# fastedge.net
KiCad netlist of a schematic drawn in EAGLE
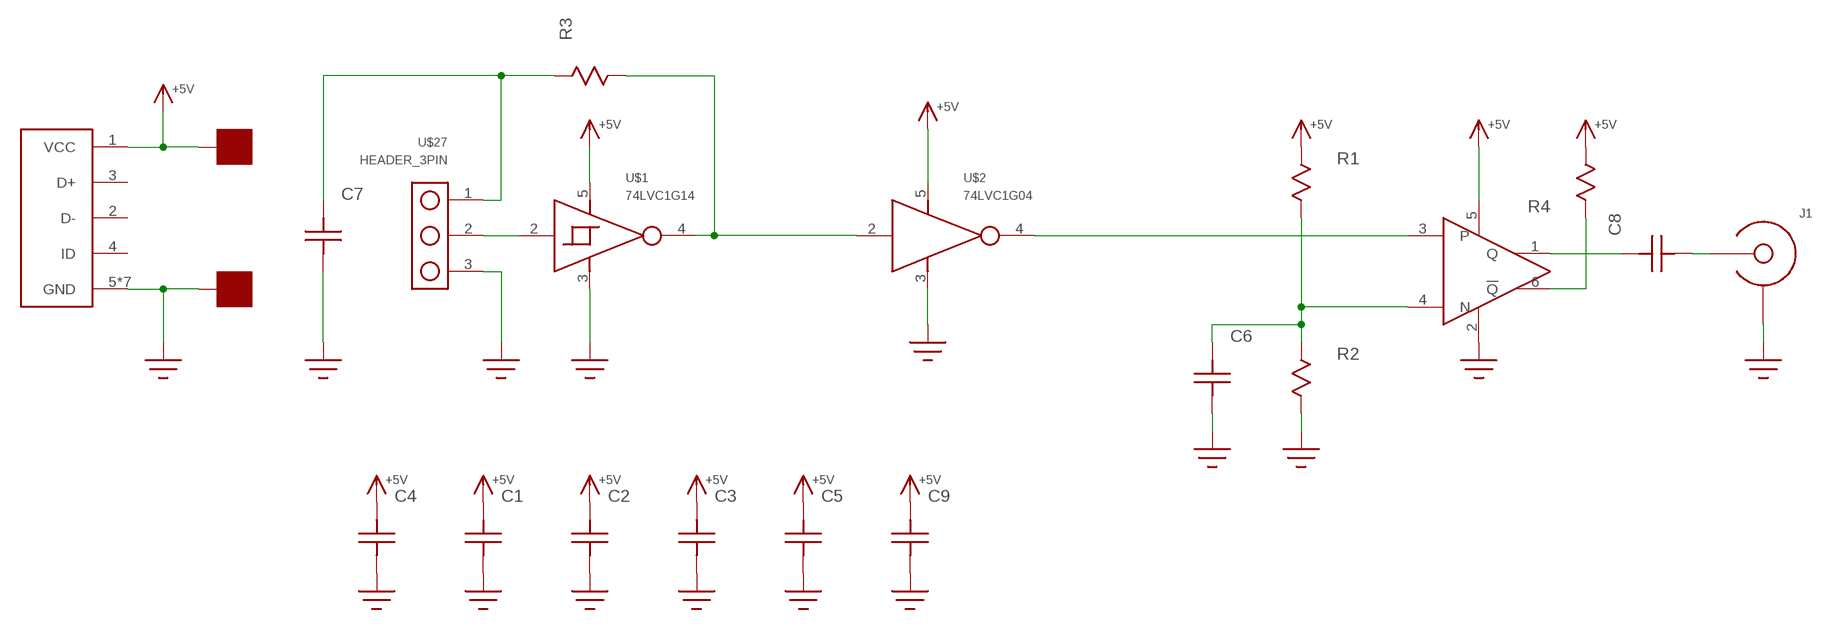
[diagram p0: schematic, sheet 1]

(export (version "E")
  (design (tool "Eeschema 10.0.6"))
  (components
    (comp (ref "C1")
      (value "C0603")
      (footprint "eagle-import:C0603")
      (libsource (lib "eagle-import") (part "C0603"))
    )
    (comp (ref "C2")
      (value "C0603")
      (footprint "eagle-import:C0603")
      (libsource (lib "eagle-import") (part "C0603"))
    )
    (comp (ref "C3")
      (value "C0603")
      (footprint "eagle-import:C0603")
      (libsource (lib "eagle-import") (part "C0603"))
    )
    (comp (ref "C4")
      (value "C0805")
      (footprint "eagle-import:0805")
      (libsource (lib "eagle-import") (part "C0805"))
    )
    (comp (ref "C5")
      (value "C0402_NO_THERMALS")
      (footprint "eagle-import:C0402_NO_THERMALS")
      (libsource (lib "eagle-import") (part "C0402_NO_THERMALS"))
    )
    (comp (ref "C6")
      (value "C0603")
      (footprint "eagle-import:C0603")
      (libsource (lib "eagle-import") (part "C0603"))
    )
    (comp (ref "C7")
      (value "C0603")
      (footprint "eagle-import:C0603")
      (libsource (lib "eagle-import") (part "C0603"))
    )
    (comp (ref "C8")
      (value "C0402_NO_THERMALS")
      (footprint "eagle-import:C0402_NO_THERMALS")
      (libsource (lib "eagle-import") (part "C0402_NO_THERMALS"))
    )
    (comp (ref "C9")
      (value "C0402_NO_THERMALS")
      (footprint "eagle-import:C0402_NO_THERMALS")
      (libsource (lib "eagle-import") (part "C0402_NO_THERMALS"))
    )
    (comp (ref "IC1")
      (value "ADCMP606")
      (footprint "eagle-import:SC70-6")
      (libsource (lib "eagle-import") (part "ADCMP606"))
    )
    (comp (ref "J1")
      (value "BNC_MALE_PCB")
      (footprint "eagle-import:BNC_MALE_PCB")
      (libsource (lib "eagle-import") (part "BNC_MALE_PCB"))
    )
    (comp (ref "R1")
      (value "R0603")
      (footprint "eagle-import:R0603")
      (libsource (lib "eagle-import") (part "R0603"))
    )
    (comp (ref "R2")
      (value "R0603")
      (footprint "eagle-import:R0603")
      (libsource (lib "eagle-import") (part "R0603"))
    )
    (comp (ref "R3")
      (value "R0603")
      (footprint "eagle-import:R0603")
      (libsource (lib "eagle-import") (part "R0603"))
    )
    (comp (ref "R4")
      (value "R0402")
      (footprint "eagle-import:0402")
      (libsource (lib "eagle-import") (part "R0402"))
    )
    (comp (ref "U$1")
      (value "74LVC1G14")
      (footprint "eagle-import:SOT23-5")
      (libsource (lib "eagle-import") (part "74LVC1G14"))
    )
    (comp (ref "U$2")
      (value "74LVC1G04")
      (footprint "eagle-import:SOT23-5")
      (libsource (lib "eagle-import") (part "74LVC1G04"))
    )
    (comp (ref "U$13")
      (value "USB_JACK")
      (footprint "eagle-import:FCI_MICRO_USB")
      (libsource (lib "eagle-import") (part "USB_JACK"))
    )
    (comp (ref "U$27")
      (value "HEADER_3PIN")
      (footprint "eagle-import:HEADER_3PIN")
      (libsource (lib "eagle-import") (part "HEADER_3PIN"))
    )
    (comp (ref "U$32")
      (value "PAD50MIL")
      (footprint "eagle-import:PAD_50MIL")
      (libsource (lib "eagle-import") (part "PAD50MIL"))
    )
    (comp (ref "U$33")
      (value "PAD50MIL")
      (footprint "eagle-import:PAD_50MIL")
      (libsource (lib "eagle-import") (part "PAD50MIL"))
    )
  )
  (nets
    (net (code "1") (name "+5V") (class "Default")
      (node (ref "C1") (pin "P$2") (pinfunction "P$2_P$2") (pintype "bidirectional"))
      (node (ref "C2") (pin "P$2") (pinfunction "P$2_P$2") (pintype "bidirectional"))
      (node (ref "C3") (pin "P$2") (pinfunction "P$2_P$2") (pintype "bidirectional"))
      (node (ref "C4") (pin "P$2") (pinfunction "P$2_P$2") (pintype "bidirectional"))
      (node (ref "C5") (pin "2") (pinfunction "P$2_2") (pintype "bidirectional"))
      (node (ref "C9") (pin "2") (pinfunction "P$2_2") (pintype "bidirectional"))
      (node (ref "IC1") (pin "5") (pinfunction "VCC_5") (pintype "bidirectional"))
      (node (ref "R1") (pin "P$1") (pinfunction "P$3_P$1") (pintype "bidirectional"))
      (node (ref "R4") (pin "2") (pinfunction "P$4_2") (pintype "bidirectional"))
      (node (ref "U$1") (pin "5") (pinfunction "VCC_5") (pintype "bidirectional"))
      (node (ref "U$13") (pin "1") (pinfunction "VCC_1") (pintype "bidirectional"))
      (node (ref "U$2") (pin "5") (pinfunction "VCC_5") (pintype "bidirectional"))
      (node (ref "U$32") (pin "P$1") (pinfunction "P$1_P$1") (pintype "bidirectional"))
    )
    (net (code "2") (name "GND") (class "Default")
      (node (ref "C1") (pin "P$1") (pinfunction "P$1_P$1") (pintype "bidirectional"))
      (node (ref "C2") (pin "P$1") (pinfunction "P$1_P$1") (pintype "bidirectional"))
      (node (ref "C3") (pin "P$1") (pinfunction "P$1_P$1") (pintype "bidirectional"))
      (node (ref "C4") (pin "P$1") (pinfunction "P$1_P$1") (pintype "bidirectional"))
      (node (ref "C5") (pin "1") (pinfunction "P$1_1") (pintype "bidirectional"))
      (node (ref "C6") (pin "P$1") (pinfunction "P$1_P$1") (pintype "bidirectional"))
      (node (ref "C7") (pin "P$1") (pinfunction "P$1_P$1") (pintype "bidirectional"))
      (node (ref "C9") (pin "1") (pinfunction "P$1_1") (pintype "bidirectional"))
      (node (ref "IC1") (pin "2") (pinfunction "VEE_2") (pintype "bidirectional"))
      (node (ref "J1") (pin "SHIELD@1") (pinfunction "SHIELD_SHIELD@1") (pintype "bidirectional"))
      (node (ref "J1") (pin "SHIELD@2") (pinfunction "SHIELD_SHIELD@2") (pintype "bidirectional"))
      (node (ref "J1") (pin "SHIELD@3") (pinfunction "SHIELD_SHIELD@3") (pintype "bidirectional"))
      (node (ref "J1") (pin "SHIELD@4") (pinfunction "SHIELD_SHIELD@4") (pintype "bidirectional"))
      (node (ref "R2") (pin "P$2") (pinfunction "P$4_P$2") (pintype "bidirectional"))
      (node (ref "U$1") (pin "3") (pinfunction "GND_3") (pintype "bidirectional"))
      (node (ref "U$13") (pin "5") (pinfunction "GND_5") (pintype "bidirectional"))
      (node (ref "U$13") (pin "GND1") (pinfunction "GND_GND1") (pintype "bidirectional"))
      (node (ref "U$13") (pin "GND2") (pinfunction "GND_GND2") (pintype "bidirectional"))
      (node (ref "U$13") (pin "GND3") (pinfunction "GND_GND3") (pintype "bidirectional"))
      (node (ref "U$13") (pin "GND4") (pinfunction "GND_GND4") (pintype "bidirectional"))
      (node (ref "U$13") (pin "GND5") (pinfunction "GND_GND5") (pintype "bidirectional"))
      (node (ref "U$13") (pin "GND6") (pinfunction "GND_GND6") (pintype "bidirectional"))
      (node (ref "U$2") (pin "3") (pinfunction "GND_3") (pintype "bidirectional"))
      (node (ref "U$27") (pin "3") (pinfunction "3_3") (pintype "bidirectional"))
      (node (ref "U$33") (pin "P$1") (pinfunction "P$1_P$1") (pintype "bidirectional"))
    )
    (net (code "3") (name "Net-(C8-P$1)") (class "Default")
      (node (ref "C8") (pin "1") (pinfunction "P$1_1") (pintype "bidirectional"))
      (node (ref "J1") (pin "CENTER") (pinfunction "CENTER_CENTER") (pintype "bidirectional"))
    )
    (net (code "4") (name "Net-(C8-P$2)") (class "Default")
      (node (ref "C8") (pin "2") (pinfunction "P$2_2") (pintype "bidirectional"))
      (node (ref "IC1") (pin "1") (pinfunction "Q_1") (pintype "bidirectional"))
    )
    (net (code "5") (name "Net-(IC1-N)") (class "Default")
      (node (ref "C6") (pin "P$2") (pinfunction "P$2_P$2") (pintype "bidirectional"))
      (node (ref "IC1") (pin "4") (pinfunction "N_4") (pintype "bidirectional"))
      (node (ref "R1") (pin "P$2") (pinfunction "P$4_P$2") (pintype "bidirectional"))
      (node (ref "R2") (pin "P$1") (pinfunction "P$3_P$1") (pintype "bidirectional"))
    )
    (net (code "6") (name "Net-(IC1-P)") (class "Default")
      (node (ref "IC1") (pin "3") (pinfunction "P_3") (pintype "bidirectional"))
      (node (ref "U$2") (pin "4") (pinfunction "OUT_4") (pintype "bidirectional"))
    )
    (net (code "7") (name "Net-(IC1-~{Q})") (class "Default")
      (node (ref "IC1") (pin "6") (pinfunction "~{Q}_6") (pintype "bidirectional"))
      (node (ref "R4") (pin "1") (pinfunction "P$3_1") (pintype "bidirectional"))
    )
    (net (code "8") (name "Net-(R3-P$3)") (class "Default")
      (node (ref "C7") (pin "P$2") (pinfunction "P$2_P$2") (pintype "bidirectional"))
      (node (ref "R3") (pin "P$1") (pinfunction "P$3_P$1") (pintype "bidirectional"))
      (node (ref "U$27") (pin "1") (pinfunction "1_1") (pintype "bidirectional"))
    )
    (net (code "9") (name "Net-(R3-P$4)") (class "Default")
      (node (ref "R3") (pin "P$2") (pinfunction "P$4_P$2") (pintype "bidirectional"))
      (node (ref "U$1") (pin "4") (pinfunction "OUT_4") (pintype "bidirectional"))
      (node (ref "U$2") (pin "2") (pinfunction "IN_2") (pintype "bidirectional"))
    )
    (net (code "10") (name "Net-(U$1-IN)") (class "Default")
      (node (ref "U$1") (pin "2") (pinfunction "IN_2") (pintype "bidirectional"))
      (node (ref "U$27") (pin "2") (pinfunction "2_2") (pintype "bidirectional"))
    )
    (net (code "11") (name "unconnected-(U$13-D+-Pad3)") (class "Default")
      (node (ref "U$13") (pin "3") (pinfunction "D+_3") (pintype "bidirectional"))
    )
    (net (code "12") (name "unconnected-(U$13-D--Pad2)") (class "Default")
      (node (ref "U$13") (pin "2") (pinfunction "D-_2") (pintype "bidirectional"))
    )
    (net (code "13") (name "unconnected-(U$13-ID-Pad4)") (class "Default")
      (node (ref "U$13") (pin "4") (pinfunction "ID_4") (pintype "bidirectional"))
    )
  )
)
